# Horn_Board.net
KiCad netlist of a schematic drawn in EAGLE
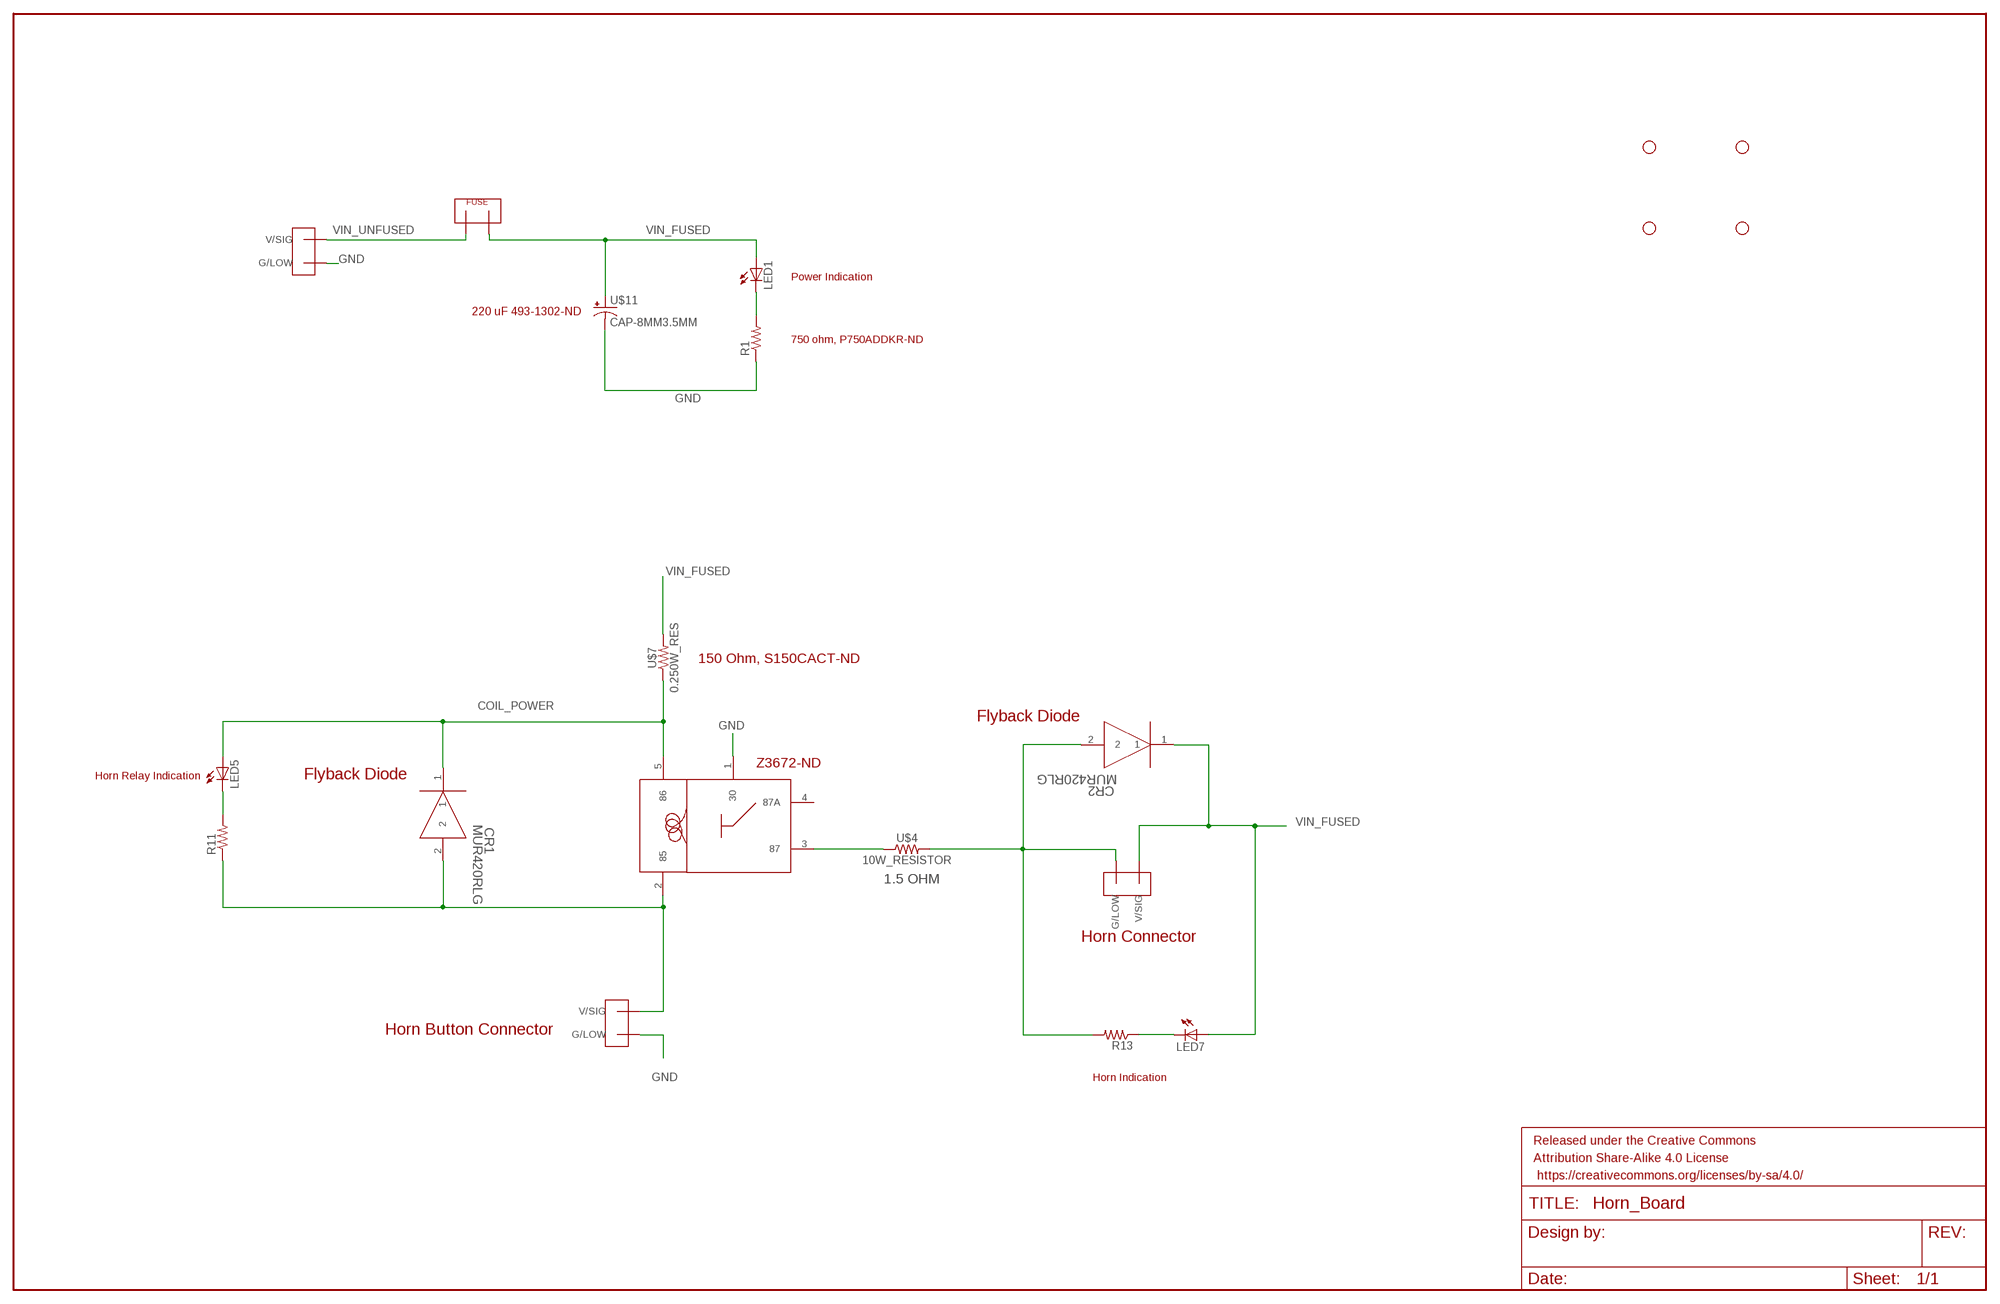
[diagram p0: schematic, sheet 1]

(export (version "E")
  (design (tool "Eeschema 10.0.6"))
  (components
    (comp (ref "CR1")
      (value "MUR420RLG")
      (footprint "eagle-import:DO-201AD")
      (libsource (lib "eagle-import") (part "MUR420RLG"))
    )
    (comp (ref "CR2")
      (value "MUR420RLG")
      (footprint "eagle-import:DO-201AD")
      (libsource (lib "eagle-import") (part "MUR420RLG"))
    )
    (comp (ref "FRAME1")
      (value "FRAME-LEDGER")
      (footprint "eagle-import:CREATIVE_COMMONS")
      (libsource (lib "eagle-import") (part "FRAME-LEDGER"))
    )
    (comp (ref "H1")
      (value "STAND-OFF")
      (footprint "eagle-import:STAND-OFF")
      (libsource (lib "eagle-import") (part "STAND-OFF"))
    )
    (comp (ref "H2")
      (value "STAND-OFF")
      (footprint "eagle-import:STAND-OFF")
      (libsource (lib "eagle-import") (part "STAND-OFF"))
    )
    (comp (ref "H3")
      (value "STAND-OFF")
      (footprint "eagle-import:STAND-OFF")
      (libsource (lib "eagle-import") (part "STAND-OFF"))
    )
    (comp (ref "H4")
      (value "STAND-OFF")
      (footprint "eagle-import:STAND-OFF")
      (libsource (lib "eagle-import") (part "STAND-OFF"))
    )
    (comp (ref "LED1")
      (value "LEDCHIP-LED0805")
      (footprint "eagle-import:CHIP-LED0805")
      (libsource (lib "eagle-import") (part "LEDCHIP-LED0805"))
    )
    (comp (ref "LED5")
      (value "LEDCHIP-LED0805")
      (footprint "eagle-import:CHIP-LED0805")
      (libsource (lib "eagle-import") (part "LEDCHIP-LED0805"))
    )
    (comp (ref "LED7")
      (value "LEDCHIP-LED0805")
      (footprint "eagle-import:CHIP-LED0805")
      (libsource (lib "eagle-import") (part "LEDCHIP-LED0805"))
    )
    (comp (ref "R1")
      (value "R-US_M0805")
      (footprint "eagle-import:M0805")
      (libsource (lib "eagle-import") (part "R-US_M0805"))
    )
    (comp (ref "R11")
      (value "R-US_M0805")
      (footprint "eagle-import:M0805")
      (libsource (lib "eagle-import") (part "R-US_M0805"))
    )
    (comp (ref "R13")
      (value "R-US_M0805")
      (footprint "eagle-import:M0805")
      (libsource (lib "eagle-import") (part "R-US_M0805"))
    )
    (comp (ref "U$1")
      (value "TE770966")
      (footprint "eagle-import:2X1-MATE-N-LOCK")
      (libsource (lib "eagle-import") (part "TE770966"))
    )
    (comp (ref "U$2")
      (value "FUSEMINI-BLADE")
      (footprint "eagle-import:MINI-BLADE-FUSE")
      (libsource (lib "eagle-import") (part "FUSEMINI-BLADE"))
    )
    (comp (ref "U$3")
      (value "OMRON_G5LE-1")
      (footprint "eagle-import:OMRON_G5LE-1")
      (libsource (lib "eagle-import") (part "OMRON_G5LE-1"))
    )
    (comp (ref "U$4")
      (value "10W_RESISTOR")
      (footprint "eagle-import:10W_RESISTOR")
      (libsource (lib "eagle-import") (part "10W_RESISTOR"))
    )
    (comp (ref "U$7")
      (value "0.250W_RES")
      (footprint "eagle-import:AXIAL-0.3")
      (libsource (lib "eagle-import") (part "0.250W_RES"))
    )
    (comp (ref "U$11")
      (value "CAP-8MM3.5MM")
      (footprint "eagle-import:CAP-8MM_3.5MM")
      (libsource (lib "eagle-import") (part "CAP-8MM3.5MM"))
    )
    (comp (ref "U$17")
      (value "TE770966")
      (footprint "eagle-import:2X1-MATE-N-LOCK")
      (libsource (lib "eagle-import") (part "TE770966"))
    )
    (comp (ref "U$18")
      (value "TE770966")
      (footprint "eagle-import:2X1-MATE-N-LOCK")
      (libsource (lib "eagle-import") (part "TE770966"))
    )
  )
  (nets
    (net (code "1") (name "/COIL_POWER") (class "Default")
      (node (ref "CR1") (pin "1") (pinfunction "1_1") (pintype "passive"))
      (node (ref "LED5") (pin "A") (pinfunction "A_A") (pintype "passive"))
      (node (ref "U$3") (pin "5") (pinfunction "86_5") (pintype "bidirectional"))
      (node (ref "U$7") (pin "P$1") (pinfunction "1_P$1") (pintype "passive"))
    )
    (net (code "2") (name "/GND") (class "Default")
      (node (ref "R1") (pin "1") (pinfunction "1_1") (pintype "passive"))
      (node (ref "U$1") (pin "CIRCUIT2") (pinfunction "G/LOW_CIRCUIT2") (pintype "bidirectional"))
      (node (ref "U$11") (pin "P$2") (pinfunction "-_P$2") (pintype "passive"))
      (node (ref "U$17") (pin "CIRCUIT2") (pinfunction "G/LOW_CIRCUIT2") (pintype "bidirectional"))
      (node (ref "U$3") (pin "1") (pinfunction "30_1") (pintype "bidirectional"))
    )
    (net (code "3") (name "/VIN_FUSED") (class "Default")
      (node (ref "CR2") (pin "1") (pinfunction "1_1") (pintype "passive"))
      (node (ref "LED1") (pin "A") (pinfunction "A_A") (pintype "passive"))
      (node (ref "LED7") (pin "A") (pinfunction "A_A") (pintype "passive"))
      (node (ref "U$11") (pin "P$1") (pinfunction "+_P$1") (pintype "passive"))
      (node (ref "U$18") (pin "CIRCUIT1") (pinfunction "V/SIG_CIRCUIT1") (pintype "bidirectional"))
      (node (ref "U$2") (pin "OUT") (pinfunction "OUT_OUT") (pintype "bidirectional"))
      (node (ref "U$7") (pin "P$2") (pinfunction "2_P$2") (pintype "passive"))
    )
    (net (code "4") (name "/VIN_UNFUSED") (class "Default")
      (node (ref "U$1") (pin "CIRCUIT1") (pinfunction "V/SIG_CIRCUIT1") (pintype "bidirectional"))
      (node (ref "U$2") (pin "IN") (pinfunction "IN_IN") (pintype "bidirectional"))
    )
    (net (code "5") (name "Net-(LED1-PadC)") (class "Default")
      (node (ref "LED1") (pin "C") (pinfunction "C_C") (pintype "passive"))
      (node (ref "R1") (pin "2") (pinfunction "2_2") (pintype "passive"))
    )
    (net (code "6") (name "Net-(LED5-PadC)") (class "Default")
      (node (ref "LED5") (pin "C") (pinfunction "C_C") (pintype "passive"))
      (node (ref "R11") (pin "2") (pinfunction "2_2") (pintype "passive"))
    )
    (net (code "7") (name "Net-(LED7-PadC)") (class "Default")
      (node (ref "LED7") (pin "C") (pinfunction "C_C") (pintype "passive"))
      (node (ref "R13") (pin "1") (pinfunction "1_1") (pintype "passive"))
    )
    (net (code "8") (name "Net-(U$3-87)") (class "Default")
      (node (ref "U$3") (pin "3") (pinfunction "87_3") (pintype "bidirectional"))
      (node (ref "U$4") (pin "P$1") (pinfunction "1_P$1") (pintype "passive"))
    )
    (net (code "9") (name "Net-(U$17-V{slash}SIG)") (class "Default")
      (node (ref "CR1") (pin "2") (pinfunction "2_2") (pintype "passive"))
      (node (ref "R11") (pin "1") (pinfunction "1_1") (pintype "passive"))
      (node (ref "U$17") (pin "CIRCUIT1") (pinfunction "V/SIG_CIRCUIT1") (pintype "bidirectional"))
      (node (ref "U$3") (pin "2") (pinfunction "85_2") (pintype "bidirectional"))
    )
    (net (code "10") (name "Net-(U$18-G{slash}LOW)") (class "Default")
      (node (ref "CR2") (pin "2") (pinfunction "2_2") (pintype "passive"))
      (node (ref "R13") (pin "2") (pinfunction "2_2") (pintype "passive"))
      (node (ref "U$18") (pin "CIRCUIT2") (pinfunction "G/LOW_CIRCUIT2") (pintype "bidirectional"))
      (node (ref "U$4") (pin "P$2") (pinfunction "2_P$2") (pintype "passive"))
    )
    (net (code "11") (name "unconnected-(U$3-87A-Pad4)") (class "Default")
      (node (ref "U$3") (pin "4") (pinfunction "87A_4") (pintype "bidirectional"))
    )
  )
)
